# PWR_GND.net
KiCad netlist of a schematic drawn in Altium Designer
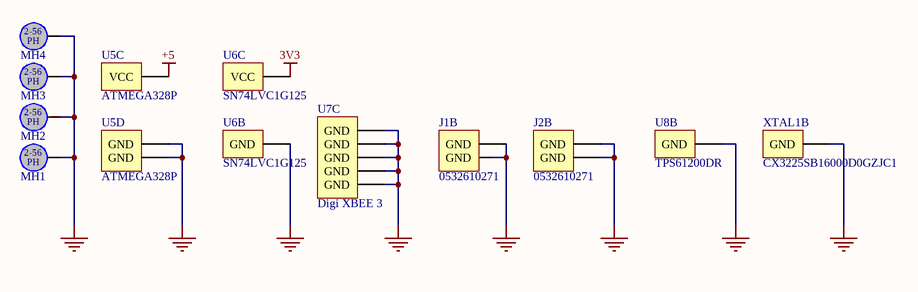
[diagram p0: PWR_GND.SchDoc]

(export (version "E")
  (design (tool "Eeschema 10.0.6"))
  (components
    (comp (ref "J1")
      (value "0532610271")
      (footprint "MOLEX_53261-0271")
      (description "2 Pos Molex Microblade")
      (fields (field (name "PART NUMBER") "0532610271"))
      (libsource (lib "Connectors") (part "0532610271"))
    )
    (comp (ref "J2")
      (value "0532610271")
      (footprint "MOLEX_53261-0271")
      (description "2 Pos Molex Microblade")
      (fields (field (name "PART NUMBER") "0532610271"))
      (libsource (lib "Connectors") (part "0532610271"))
    )
    (comp (ref "MH1")
      (value "MH_2-56_PanHead_CloseFit")
      (footprint "MH_2-56_PH")
      (description "Mounting Hole, 2-56 Pan Head, Close Fit Hole")
      (fields (field (name "MANF") "None"))
      (libsource (lib "Connectors") (part "MH_2-56_PanHead_CloseFit"))
    )
    (comp (ref "MH2")
      (value "MH_2-56_PanHead_CloseFit")
      (footprint "MH_2-56_PH")
      (description "Mounting Hole, 2-56 Pan Head, Close Fit Hole")
      (fields (field (name "MANF") "None"))
      (libsource (lib "Connectors") (part "MH_2-56_PanHead_CloseFit"))
    )
    (comp (ref "MH3")
      (value "MH_2-56_PanHead_CloseFit")
      (footprint "MH_2-56_PH")
      (description "Mounting Hole, 2-56 Pan Head, Close Fit Hole")
      (fields (field (name "MANF") "None"))
      (libsource (lib "Connectors") (part "MH_2-56_PanHead_CloseFit"))
    )
    (comp (ref "MH4")
      (value "MH_2-56_PanHead_CloseFit")
      (footprint "MH_2-56_PH")
      (description "Mounting Hole, 2-56 Pan Head, Close Fit Hole")
      (fields (field (name "MANF") "None"))
      (libsource (lib "Connectors") (part "MH_2-56_PanHead_CloseFit"))
    )
    (comp (ref "U5")
      (value "ATMEGA328P_SMD")
      (footprint "32A_ATM")
      (description "Arduino ATMEGA328 Chip")
      (fields (field (name "PART NUMBER") "ATMEGA328P"))
      (libsource (lib "ICs") (part "ATMEGA328P_SMD"))
    )
    (comp (ref "U6")
      (value "SN74LVC1G125DCKR")
      (footprint "SOT-SC70-5")
      (description "Single Bus 3-State Buffer")
      (fields (field (name "PART NUMBER") "SN74LVC1G125"))
      (libsource (lib "") (part "SN74LVC1G125DCKR_1"))
    )
    (comp (ref "U7")
      (value "XBEE 3 SMD")
      (footprint "XBee_1W_Base")
      (fields (field (name "PART NUMBER") "Digi XBEE 3"))
      (libsource (lib "ICs") (part "XBEE 3 SMD"))
    )
    (comp (ref "U8")
      (value "TPS61200DR Voltage Boost Regulator")
      (footprint "10-VFDFN Exposed Pad")
      (description "Used on Pololu step up regulator board")
      (fields (field (name "PART NUMBER") "TPS61200DR"))
      (libsource (lib "ICs") (part "TPS61200DR Voltage Boost Regulator"))
    )
    (comp (ref "XTAL1")
      (value "CX3225SB16000D0GZJC1")
      (footprint "OSC SMD-4")
      (description "16MHz Oscillator")
      (libsource (lib "Actives") (part "CX3225SB16000D0GZJC1"))
    )
  )
  (nets
    (net (code "1") (name "+5") (class "Default")
      (node (ref "U5") (pin "6") (pinfunction "VCC_6") (pintype "power_in"))
    )
    (net (code "2") (name "3V3") (class "Default")
      (node (ref "U6") (pin "5") (pinfunction "VCC_5") (pintype "power_in"))
    )
    (net (code "3") (name "GND") (class "Default")
      (node (ref "J1") (pin "P1") (pinfunction "GND_P1") (pintype "passive"))
      (node (ref "J1") (pin "P2") (pinfunction "GND_P2") (pintype "passive"))
      (node (ref "J2") (pin "P1") (pinfunction "GND_P1") (pintype "passive"))
      (node (ref "J2") (pin "P2") (pinfunction "GND_P2") (pintype "passive"))
      (node (ref "MH1") (pin "1") (pinfunction "1_1") (pintype "passive"))
      (node (ref "MH2") (pin "1") (pinfunction "1_1") (pintype "passive"))
      (node (ref "MH3") (pin "1") (pinfunction "1_1") (pintype "passive"))
      (node (ref "MH4") (pin "1") (pinfunction "1_1") (pintype "passive"))
      (node (ref "U5") (pin "21") (pinfunction "GND_21") (pintype "power_in"))
      (node (ref "U5") (pin "3") (pinfunction "GND_3") (pintype "power_in"))
      (node (ref "U6") (pin "3") (pinfunction "GND_3") (pintype "passive"))
      (node (ref "U7") (pin "1") (pinfunction "GND_1") (pintype "power_in"))
      (node (ref "U7") (pin "11") (pinfunction "GND_11") (pintype "power_in"))
      (node (ref "U7") (pin "22") (pinfunction "GND_22") (pintype "power_in"))
      (node (ref "U7") (pin "35") (pinfunction "GND_35") (pintype "power_in"))
      (node (ref "U7") (pin "38") (pinfunction "GND_38") (pintype "power_in"))
      (node (ref "U8") (pin "9") (pinfunction "GND_9") (pintype "power_in"))
      (node (ref "XTAL1") (pin "4") (pinfunction "GND_4") (pintype "passive"))
    )
  )
)
